# Bluetooth.net
KiCad netlist of a schematic drawn in Altium Designer
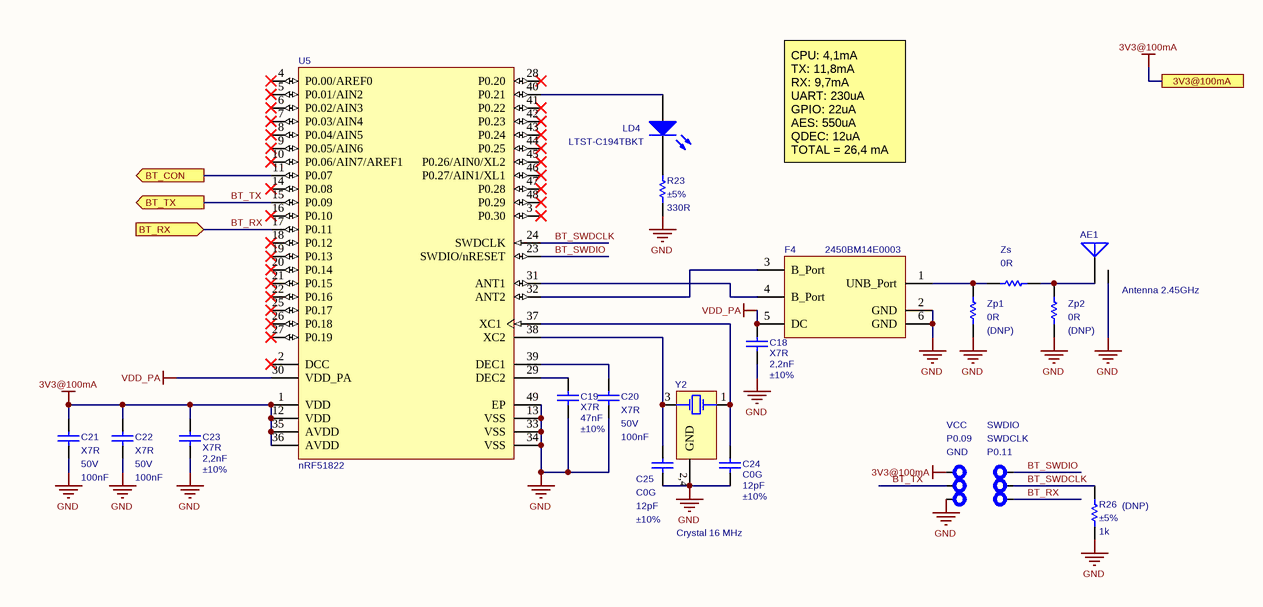
[diagram p0: Bluetooth.SchDoc]

(export (version "E")
  (design (tool "Eeschema 10.0.6"))
  (components
    (comp (ref "AE1")
      (value "Antenna 2.45GHz")
      (footprint "MIFA_2.45GHz_7.2x11.1mm")
      (description "MIFA Antenna 2.45GHz")
      (libsource (lib "BQ Vault") (part "Antenna_diff"))
    )
    (comp (ref "C18")
      (value "C0402_2.2nF_16V_±10%")
      (footprint "C0402")
      (fields
        (field (name "DIELECTRIC") "X7R")
        (field (name "VOLTAGE") "16V")
        (field (name "CAPACITANCE") "2,2nF")
        (field (name "TOLERANCE") "±10%")
        (field (name "MANUFACTURER") "Kemet")
      )
      (libsource (lib "BQ Vault") (part "Capacitor"))
    )
    (comp (ref "C19")
      (value "C0402_47nF_16V_±10%")
      (footprint "C0402")
      (fields
        (field (name "DIELECTRIC") "X7R")
        (field (name "VOLTAGE") "16V")
        (field (name "CAPACITANCE") "47nF")
        (field (name "TOLERANCE") "±10%")
        (field (name "MANUFACTURER") "Kemet")
      )
      (libsource (lib "BQ Vault") (part "Capacitor"))
    )
    (comp (ref "C20")
      (value "C0603_100nF_50V_±10%_X7R")
      (footprint "C0603")
      (fields
        (field (name "DIELECTRIC") "X7R")
        (field (name "VOLTAGE") "50V")
        (field (name "CAPACITANCE") "100nF")
        (field (name "MANUFACTURER") "Kemet")
        (field (name "TOLERANCE") "±10%")
      )
      (libsource (lib "BQ Vault") (part "CMP-00257-1"))
    )
    (comp (ref "C21")
      (value "C0603_100nF_50V_±10%_X7R")
      (footprint "C0603")
      (fields
        (field (name "DIELECTRIC") "X7R")
        (field (name "VOLTAGE") "50V")
        (field (name "CAPACITANCE") "100nF")
        (field (name "MANUFACTURER") "Kemet")
        (field (name "TOLERANCE") "±10%")
      )
      (libsource (lib "BQ Vault") (part "CMP-00257-1"))
    )
    (comp (ref "C22")
      (value "C0603_100nF_50V_±10%_X7R")
      (footprint "C0603")
      (fields
        (field (name "DIELECTRIC") "X7R")
        (field (name "VOLTAGE") "50V")
        (field (name "CAPACITANCE") "100nF")
        (field (name "MANUFACTURER") "Kemet")
        (field (name "TOLERANCE") "±10%")
      )
      (libsource (lib "BQ Vault") (part "CMP-00257-1"))
    )
    (comp (ref "C23")
      (value "C0402_2.2nF_16V_±10%")
      (footprint "C0402")
      (fields
        (field (name "DIELECTRIC") "X7R")
        (field (name "VOLTAGE") "16V")
        (field (name "CAPACITANCE") "2,2nF")
        (field (name "TOLERANCE") "±10%")
        (field (name "MANUFACTURER") "Kemet")
      )
      (libsource (lib "BQ Vault") (part "Capacitor"))
    )
    (comp (ref "C24")
      (value "C0402_12pF_16V_±10%")
      (footprint "C0402")
      (fields
        (field (name "DIELECTRIC") "C0G")
        (field (name "VOLTAGE") "16V")
        (field (name "CAPACITANCE") "12pF")
        (field (name "TOLERANCE") "±10%")
        (field (name "MANUFACTURER") "Kemet")
      )
      (libsource (lib "BQ Vault") (part "Capacitor"))
    )
    (comp (ref "C25")
      (value "C0402_12pF_16V_±10%")
      (footprint "C0402")
      (fields
        (field (name "DIELECTRIC") "C0G")
        (field (name "VOLTAGE") "16V")
        (field (name "CAPACITANCE") "12pF")
        (field (name "TOLERANCE") "±10%")
        (field (name "MANUFACTURER") "Kemet")
      )
      (libsource (lib "BQ Vault") (part "Capacitor"))
    )
    (comp (ref "F4")
      (value "2450BM14E0003")
      (footprint "BAL-0603-6PIN")
      (description "2.45GHz Impedance Matched Balun + Band Pass Filter")
      (fields (field (name "MANUFACTURER") "Johanson"))
      (libsource (lib "BQ Vault") (part "2450BM14E0003"))
    )
    (comp (ref "GND")
      (value "TP_POWER")
      (footprint "TP_POWER")
      (description "Testpoint 0.3mm")
      (fields (field (name "MANUFACTURER") "Oxley"))
      (libsource (lib "BQ Vault") (part "CMP-A2499-3"))
    )
    (comp (ref "LD4")
      (value "LTST-C194TBKT")
      (footprint "LED0603")
      (description "LED")
      (fields (field (name "MANUFACTURER") "Lite-On"))
      (libsource (lib "BQ Vault") (part "LED"))
    )
    (comp (ref "P0.09")
      (value "TP_POWER")
      (footprint "TP_POWER")
      (description "Testpoint 0.3mm")
      (fields (field (name "MANUFACTURER") "Oxley"))
      (libsource (lib "BQ Vault") (part "CMP-A2499-3"))
    )
    (comp (ref "P0.11")
      (value "TP_POWER")
      (footprint "TP_POWER")
      (description "Testpoint 0.3mm")
      (fields (field (name "MANUFACTURER") "Oxley"))
      (libsource (lib "BQ Vault") (part "CMP-A2499-3"))
    )
    (comp (ref "R23")
      (value "R0402_330R_0.063W_±5%")
      (footprint "R0402")
      (fields
        (field (name "TOLERANCE") "±5%")
        (field (name "POWER") "0.063W")
        (field (name "RESISTANCE") "330R")
        (field (name "MANUFACTURER") "Vishay")
      )
      (libsource (lib "BQ Vault") (part "CMP-A1762-2"))
    )
    (comp (ref "R26")
      (value "R0402_1k_0.063W_±5%")
      (footprint "R0402")
      (fields
        (field (name "TOLERANCE") "±5%")
        (field (name "POWER") "0.063W")
        (field (name "RESISTANCE") "1k")
        (field (name "MANUFACTURER") "Vishay")
        (field (name "VARIANT") "(DNP)")
      )
      (libsource (lib "BQ Vault") (part "CMP-A1718-3"))
    )
    (comp (ref "SWDCLK")
      (value "TP_POWER")
      (footprint "TP_POWER")
      (description "Testpoint 0.3mm")
      (fields (field (name "MANUFACTURER") "Oxley"))
      (libsource (lib "BQ Vault") (part "CMP-A2499-3"))
    )
    (comp (ref "SWDIO")
      (value "TP_POWER")
      (footprint "TP_POWER")
      (description "Testpoint 0.3mm")
      (fields (field (name "MANUFACTURER") "Oxley"))
      (libsource (lib "BQ Vault") (part "CMP-A2499-3"))
    )
    (comp (ref "U5")
      (value "nRF51822")
      (footprint "QFN_48_6x6mm")
      (description "Multiprotocol Bluetooth® low energy/2.4 GHz RF System on Chip")
      (fields (field (name "MANUFACTURER") "Nordic"))
      (libsource (lib "BQ Vault") (part "CMP-00292-1"))
    )
    (comp (ref "VCC")
      (value "TP_POWER")
      (footprint "TP_POWER")
      (description "Testpoint 0.3mm")
      (fields (field (name "MANUFACTURER") "Oxley"))
      (libsource (lib "BQ Vault") (part "CMP-A2499-3"))
    )
    (comp (ref "Y2")
      (value "Crystal 16 MHz")
      (footprint "ABM8G_3.2x2.5mm")
      (fields
        (field (name "PART NUMBER") "ABM8G 16MHz")
        (field (name "TOLERANCE") "±30ppm")
        (field (name "MANUFACTURER") "Abracon")
      )
      (libsource (lib "BQ Vault") (part "Crystal 4 pin"))
    )
    (comp (ref "Zp1")
      (value "R0402_0R_0.063W_±5%")
      (footprint "R0402")
      (fields
        (field (name "POWER") "0.063W")
        (field (name "RESISTANCE") "0R")
        (field (name "MANUFACTURER") "Panasonic")
        (field (name "TOLERANCE") "±5%")
        (field (name "VARIANT") "(DNP)")
      )
      (libsource (lib "BQ Vault") (part "CMP-A1689-4"))
    )
    (comp (ref "Zp2")
      (value "R0402_0R_0.063W_±5%")
      (footprint "R0402")
      (fields
        (field (name "POWER") "0.063W")
        (field (name "RESISTANCE") "0R")
        (field (name "MANUFACTURER") "Panasonic")
        (field (name "TOLERANCE") "±5%")
        (field (name "VARIANT") "(DNP)")
      )
      (libsource (lib "BQ Vault") (part "CMP-A1689-4"))
    )
    (comp (ref "Zs")
      (value "R0402_0R_0.063W_±5%")
      (footprint "R0402")
      (fields
        (field (name "POWER") "0.063W")
        (field (name "RESISTANCE") "0R")
        (field (name "MANUFACTURER") "Panasonic")
        (field (name "TOLERANCE") "±5%")
      )
      (libsource (lib "BQ Vault") (part "CMP-A1689-4"))
    )
  )
  (nets
    (net (code "1") (name "/BT_CON") (class "Default")
      (node (ref "U5") (pin "11") (pinfunction "P0.07_11") (pintype "bidirectional"))
    )
    (net (code "2") (name "/BT_RX") (class "Default")
      (node (ref "P0.11") (pin "1") (pinfunction "1_1") (pintype "passive"))
      (node (ref "U5") (pin "17") (pinfunction "P0.11_17") (pintype "bidirectional"))
    )
    (net (code "3") (name "/BT_SWDCLK") (class "Default")
      (node (ref "R26") (pin "2") (pinfunction "2_2") (pintype "passive"))
      (node (ref "SWDCLK") (pin "1") (pinfunction "1_1") (pintype "passive"))
      (node (ref "U5") (pin "24") (pinfunction "SWDCLK_24") (pintype "input"))
    )
    (net (code "4") (name "/BT_SWDIO") (class "Default")
      (node (ref "SWDIO") (pin "1") (pinfunction "1_1") (pintype "passive"))
      (node (ref "U5") (pin "23") (pinfunction "SWDIO/nRESET_23") (pintype "bidirectional"))
    )
    (net (code "5") (name "/BT_TX") (class "Default")
      (node (ref "P0.09") (pin "1") (pinfunction "1_1") (pintype "passive"))
      (node (ref "U5") (pin "15") (pinfunction "P0.09_15") (pintype "bidirectional"))
    )
    (net (code "6") (name "3V3@100mA") (class "Default")
      (node (ref "C21") (pin "2") (pinfunction "2_2") (pintype "passive"))
      (node (ref "C22") (pin "2") (pinfunction "2_2") (pintype "passive"))
      (node (ref "C23") (pin "2") (pinfunction "2_2") (pintype "passive"))
      (node (ref "U5") (pin "1") (pinfunction "VDD_1") (pintype "power_in"))
      (node (ref "U5") (pin "12") (pinfunction "VDD_12") (pintype "power_in"))
      (node (ref "U5") (pin "35") (pinfunction "AVDD_35") (pintype "power_in"))
      (node (ref "U5") (pin "36") (pinfunction "AVDD_36") (pintype "power_in"))
      (node (ref "VCC") (pin "1") (pinfunction "1_1") (pintype "passive"))
    )
    (net (code "7") (name "GND") (class "Default")
      (node (ref "AE1") (pin "FEED_2") (pinfunction "FEED_2_FEED_2") (pintype "passive"))
      (node (ref "C18") (pin "1") (pinfunction "1_1") (pintype "passive"))
      (node (ref "C19") (pin "1") (pinfunction "1_1") (pintype "passive"))
      (node (ref "C20") (pin "1") (pinfunction "1_1") (pintype "passive"))
      (node (ref "C21") (pin "1") (pinfunction "1_1") (pintype "passive"))
      (node (ref "C22") (pin "1") (pinfunction "1_1") (pintype "passive"))
      (node (ref "C23") (pin "1") (pinfunction "1_1") (pintype "passive"))
      (node (ref "C24") (pin "2") (pinfunction "2_2") (pintype "passive"))
      (node (ref "C25") (pin "2") (pinfunction "2_2") (pintype "passive"))
      (node (ref "F4") (pin "2") (pinfunction "GND_2") (pintype "power_in"))
      (node (ref "F4") (pin "6") (pinfunction "GND_6") (pintype "power_in"))
      (node (ref "GND") (pin "1") (pinfunction "1_1") (pintype "passive"))
      (node (ref "R23") (pin "2") (pinfunction "2_2") (pintype "passive"))
      (node (ref "R26") (pin "1") (pinfunction "1_1") (pintype "passive"))
      (node (ref "U5") (pin "13") (pinfunction "VSS_13") (pintype "power_in"))
      (node (ref "U5") (pin "33") (pinfunction "VSS_33") (pintype "power_in"))
      (node (ref "U5") (pin "34") (pinfunction "VSS_34") (pintype "power_in"))
      (node (ref "U5") (pin "49") (pinfunction "EP_49") (pintype "power_in"))
      (node (ref "Y2") (pin "2") (pinfunction "GND_2") (pintype "passive"))
      (node (ref "Y2") (pin "4") (pinfunction "GND_4") (pintype "passive"))
      (node (ref "Zp1") (pin "1") (pinfunction "1_1") (pintype "passive"))
      (node (ref "Zp2") (pin "1") (pinfunction "1_1") (pintype "passive"))
    )
    (net (code "8") (name "Net-(AE1-PadFEED_1)") (class "Default")
      (node (ref "AE1") (pin "FEED_1") (pinfunction "FEED_1_FEED_1") (pintype "passive"))
      (node (ref "Zp2") (pin "2") (pinfunction "2_2") (pintype "passive"))
      (node (ref "Zs") (pin "2") (pinfunction "2_2") (pintype "passive"))
    )
    (net (code "9") (name "Net-(F4-UNB_Port)") (class "Default")
      (node (ref "F4") (pin "1") (pinfunction "UNB_Port_1") (pintype "passive"))
      (node (ref "Zp1") (pin "2") (pinfunction "2_2") (pintype "passive"))
      (node (ref "Zs") (pin "1") (pinfunction "1_1") (pintype "passive"))
    )
    (net (code "10") (name "Net-(LD4-PadK)") (class "Default")
      (node (ref "LD4") (pin "K") (pinfunction "K_K") (pintype "passive"))
      (node (ref "R23") (pin "1") (pinfunction "1_1") (pintype "passive"))
    )
    (net (code "11") (name "Net-(U5-ANT1)") (class "Default")
      (node (ref "F4") (pin "4") (pinfunction "B_Port_4") (pintype "passive"))
      (node (ref "U5") (pin "31") (pinfunction "ANT1_31") (pintype "bidirectional"))
    )
    (net (code "12") (name "Net-(U5-ANT2)") (class "Default")
      (node (ref "F4") (pin "3") (pinfunction "B_Port_3") (pintype "passive"))
      (node (ref "U5") (pin "32") (pinfunction "ANT2_32") (pintype "bidirectional"))
    )
    (net (code "13") (name "Net-(U5-DEC1)") (class "Default")
      (node (ref "C20") (pin "2") (pinfunction "2_2") (pintype "passive"))
      (node (ref "U5") (pin "39") (pinfunction "DEC1_39") (pintype "passive"))
    )
    (net (code "14") (name "Net-(U5-DEC2)") (class "Default")
      (node (ref "C19") (pin "2") (pinfunction "2_2") (pintype "passive"))
      (node (ref "U5") (pin "29") (pinfunction "DEC2_29") (pintype "passive"))
    )
    (net (code "15") (name "Net-(U5-P0.21)") (class "Default")
      (node (ref "LD4") (pin "A") (pinfunction "A_A") (pintype "passive"))
      (node (ref "U5") (pin "40") (pinfunction "P0.21_40") (pintype "bidirectional"))
    )
    (net (code "16") (name "Net-(U5-XC1)") (class "Default")
      (node (ref "C24") (pin "1") (pinfunction "1_1") (pintype "passive"))
      (node (ref "U5") (pin "37") (pinfunction "XC1_37") (pintype "input"))
      (node (ref "Y2") (pin "1") (pinfunction "OSC1_1") (pintype "passive"))
    )
    (net (code "17") (name "Net-(U5-XC2)") (class "Default")
      (node (ref "C25") (pin "1") (pinfunction "1_1") (pintype "passive"))
      (node (ref "U5") (pin "38") (pinfunction "XC2_38") (pintype "passive"))
      (node (ref "Y2") (pin "3") (pinfunction "OSC2_3") (pintype "passive"))
    )
    (net (code "18") (name "VDD_PA") (class "Default")
      (node (ref "C18") (pin "2") (pinfunction "2_2") (pintype "passive"))
      (node (ref "F4") (pin "5") (pinfunction "DC_5") (pintype "power_in"))
      (node (ref "U5") (pin "30") (pinfunction "VDD_PA_30") (pintype "power_in"))
    )
    (net (code "19") (name "unconnected-(U5-DCC-Pad2)") (class "Default")
      (node (ref "U5") (pin "2") (pinfunction "DCC_2") (pintype "power_in+no_connect"))
    )
    (net (code "20") (name "unconnected-(U5-P0.00{slash}AREF0-Pad4)") (class "Default")
      (node (ref "U5") (pin "4") (pinfunction "P0.00/AREF0_4") (pintype "bidirectional+no_connect"))
    )
    (net (code "21") (name "unconnected-(U5-P0.01{slash}AIN2-Pad5)") (class "Default")
      (node (ref "U5") (pin "5") (pinfunction "P0.01/AIN2_5") (pintype "bidirectional+no_connect"))
    )
    (net (code "22") (name "unconnected-(U5-P0.02{slash}AIN3-Pad6)") (class "Default")
      (node (ref "U5") (pin "6") (pinfunction "P0.02/AIN3_6") (pintype "bidirectional+no_connect"))
    )
    (net (code "23") (name "unconnected-(U5-P0.03{slash}AIN4-Pad7)") (class "Default")
      (node (ref "U5") (pin "7") (pinfunction "P0.03/AIN4_7") (pintype "bidirectional+no_connect"))
    )
    (net (code "24") (name "unconnected-(U5-P0.04{slash}AIN5-Pad8)") (class "Default")
      (node (ref "U5") (pin "8") (pinfunction "P0.04/AIN5_8") (pintype "bidirectional+no_connect"))
    )
    (net (code "25") (name "unconnected-(U5-P0.05{slash}AIN6-Pad9)") (class "Default")
      (node (ref "U5") (pin "9") (pinfunction "P0.05/AIN6_9") (pintype "bidirectional+no_connect"))
    )
    (net (code "26") (name "unconnected-(U5-P0.06{slash}AIN7{slash}AREF1-Pad10)") (class "Default")
      (node (ref "U5") (pin "10") (pinfunction "P0.06/AIN7/AREF1_10") (pintype "bidirectional+no_connect"))
    )
    (net (code "27") (name "unconnected-(U5-P0.08-Pad14)") (class "Default")
      (node (ref "U5") (pin "14") (pinfunction "P0.08_14") (pintype "bidirectional+no_connect"))
    )
    (net (code "28") (name "unconnected-(U5-P0.10-Pad16)") (class "Default")
      (node (ref "U5") (pin "16") (pinfunction "P0.10_16") (pintype "bidirectional+no_connect"))
    )
    (net (code "29") (name "unconnected-(U5-P0.12-Pad18)") (class "Default")
      (node (ref "U5") (pin "18") (pinfunction "P0.12_18") (pintype "bidirectional+no_connect"))
    )
    (net (code "30") (name "unconnected-(U5-P0.13-Pad19)") (class "Default")
      (node (ref "U5") (pin "19") (pinfunction "P0.13_19") (pintype "bidirectional+no_connect"))
    )
    (net (code "31") (name "unconnected-(U5-P0.14-Pad20)") (class "Default")
      (node (ref "U5") (pin "20") (pinfunction "P0.14_20") (pintype "bidirectional+no_connect"))
    )
    (net (code "32") (name "unconnected-(U5-P0.15-Pad21)") (class "Default")
      (node (ref "U5") (pin "21") (pinfunction "P0.15_21") (pintype "bidirectional+no_connect"))
    )
    (net (code "33") (name "unconnected-(U5-P0.16-Pad22)") (class "Default")
      (node (ref "U5") (pin "22") (pinfunction "P0.16_22") (pintype "bidirectional+no_connect"))
    )
    (net (code "34") (name "unconnected-(U5-P0.17-Pad25)") (class "Default")
      (node (ref "U5") (pin "25") (pinfunction "P0.17_25") (pintype "bidirectional+no_connect"))
    )
    (net (code "35") (name "unconnected-(U5-P0.18-Pad26)") (class "Default")
      (node (ref "U5") (pin "26") (pinfunction "P0.18_26") (pintype "bidirectional+no_connect"))
    )
    (net (code "36") (name "unconnected-(U5-P0.19-Pad27)") (class "Default")
      (node (ref "U5") (pin "27") (pinfunction "P0.19_27") (pintype "bidirectional+no_connect"))
    )
    (net (code "37") (name "unconnected-(U5-P0.20-Pad28)") (class "Default")
      (node (ref "U5") (pin "28") (pinfunction "P0.20_28") (pintype "bidirectional+no_connect"))
    )
    (net (code "38") (name "unconnected-(U5-P0.22-Pad41)") (class "Default")
      (node (ref "U5") (pin "41") (pinfunction "P0.22_41") (pintype "bidirectional+no_connect"))
    )
    (net (code "39") (name "unconnected-(U5-P0.23-Pad42)") (class "Default")
      (node (ref "U5") (pin "42") (pinfunction "P0.23_42") (pintype "bidirectional+no_connect"))
    )
    (net (code "40") (name "unconnected-(U5-P0.24-Pad43)") (class "Default")
      (node (ref "U5") (pin "43") (pinfunction "P0.24_43") (pintype "bidirectional+no_connect"))
    )
    (net (code "41") (name "unconnected-(U5-P0.25-Pad44)") (class "Default")
      (node (ref "U5") (pin "44") (pinfunction "P0.25_44") (pintype "bidirectional+no_connect"))
    )
    (net (code "42") (name "unconnected-(U5-P0.26{slash}AIN0{slash}XL2-Pad45)") (class "Default")
      (node (ref "U5") (pin "45") (pinfunction "P0.26/AIN0/XL2_45") (pintype "bidirectional+no_connect"))
    )
    (net (code "43") (name "unconnected-(U5-P0.27{slash}AIN1{slash}XL1-Pad46)") (class "Default")
      (node (ref "U5") (pin "46") (pinfunction "P0.27/AIN1/XL1_46") (pintype "bidirectional+no_connect"))
    )
    (net (code "44") (name "unconnected-(U5-P0.28-Pad47)") (class "Default")
      (node (ref "U5") (pin "47") (pinfunction "P0.28_47") (pintype "bidirectional+no_connect"))
    )
    (net (code "45") (name "unconnected-(U5-P0.29-Pad48)") (class "Default")
      (node (ref "U5") (pin "48") (pinfunction "P0.29_48") (pintype "bidirectional+no_connect"))
    )
    (net (code "46") (name "unconnected-(U5-P0.30-Pad3)") (class "Default")
      (node (ref "U5") (pin "3") (pinfunction "P0.30_3") (pintype "bidirectional+no_connect"))
    )
  )
)
